# IIC.net
KiCad netlist of a schematic drawn in Altium Designer
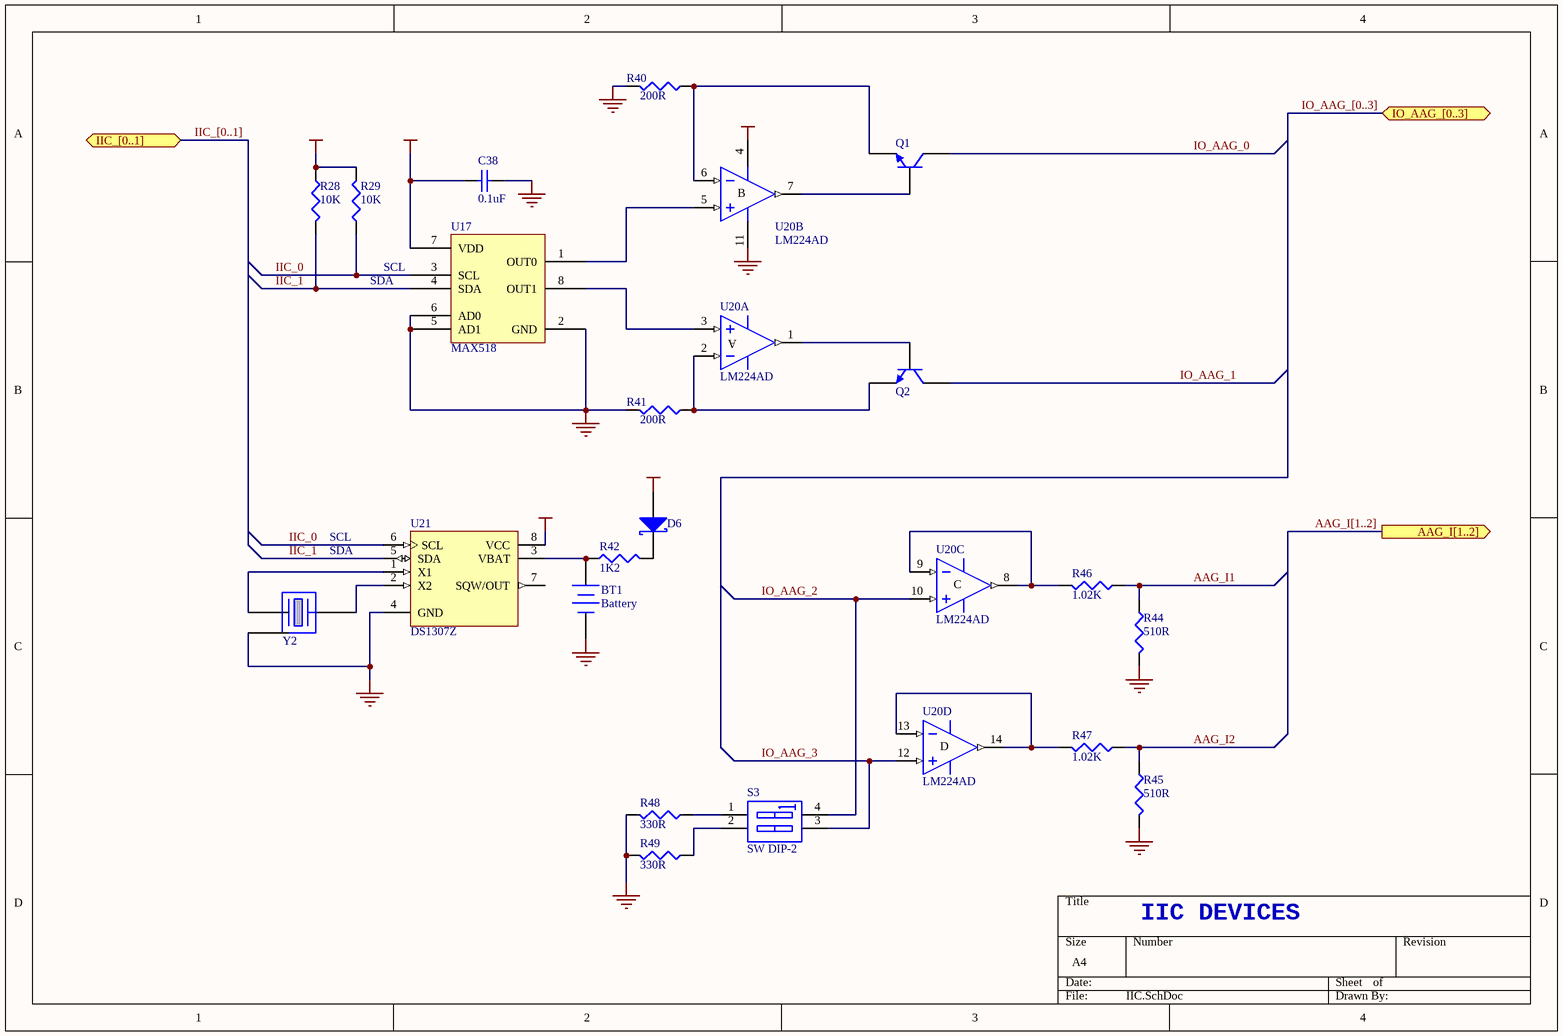
[diagram p0: IIC.SchDoc]

(export (version "E")
  (design (tool "Eeschema 10.0.6"))
  (components
    (comp (ref "BT1")
      (value "Battery")
      (footprint "LITHIUM_BAT")
      (description "Multicell Battery")
      (fields (field (name "PUBLISHER") "Altium Limited"))
      (libsource (lib "Miscellaneous Devices") (part "Battery"))
    )
    (comp (ref "C38")
      (value "0.1uF")
      (footprint "_0805")
      (description "Capacitor (Semiconductor SIM Model)")
      (fields (field (name "Comment") "Cap Semi") (field (name "PUBLISHER") "Altium Limited"))
      (libsource (lib "Miscellaneous Devices") (part "Cap Semi"))
    )
    (comp (ref "D6")
      (value "Diode BAS70")
      (footprint "SO-G3/C2.5")
      (description "Silicon AF Schottky Diode for High-Speed Switching")
      (fields (field (name "PUBLISHER") "Altium Limited"))
      (libsource (lib "Miscellaneous Devices") (part "Diode BAS70"))
    )
    (comp (ref "Q1")
      (value "QNPN")
      (footprint "SO-G3/C2.5")
      (description "NPN Bipolar Transistor")
      (fields (field (name "PUBLISHER") "Altium Limited"))
      (libsource (lib "") (part "QNPN_1"))
    )
    (comp (ref "Q2")
      (value "QNPN")
      (footprint "SO-G3/C2.5")
      (description "NPN Bipolar Transistor")
      (fields (field (name "PUBLISHER") "Altium Limited"))
      (libsource (lib "Miscellaneous Devices") (part "QNPN"))
    )
    (comp (ref "R28")
      (value "10K")
      (footprint "_0805")
      (description "Resistor")
      (fields (field (name "Comment") "Res3") (field (name "PUBLISHER") "Altium Limited"))
      (libsource (lib "") (part "Res3_1"))
    )
    (comp (ref "R29")
      (value "10K")
      (footprint "_0805")
      (description "Resistor")
      (fields (field (name "Comment") "Res3") (field (name "PUBLISHER") "Altium Limited"))
      (libsource (lib "") (part "Res3_1"))
    )
    (comp (ref "R40")
      (value "200R")
      (footprint "_1206")
      (description "Resistor")
      (fields (field (name "Comment") "Res3") (field (name "PUBLISHER") "Altium Limited"))
      (libsource (lib "") (part "Res3_1"))
    )
    (comp (ref "R41")
      (value "200R")
      (footprint "_1206")
      (description "Resistor")
      (fields (field (name "Comment") "Res3") (field (name "PUBLISHER") "Altium Limited"))
      (libsource (lib "") (part "Res3_1"))
    )
    (comp (ref "R42")
      (value "1K2")
      (footprint "_0805")
      (description "Resistor")
      (fields (field (name "Comment") "Res3") (field (name "PUBLISHER") "Altium Limited"))
      (libsource (lib "") (part "Res3_1"))
    )
    (comp (ref "R44")
      (value "510R")
      (footprint "_0805")
      (description "Resistor")
      (fields (field (name "Comment") "Res3") (field (name "PUBLISHER") "Altium Limited"))
      (libsource (lib "") (part "Res3_1"))
    )
    (comp (ref "R45")
      (value "510R")
      (footprint "_0805")
      (description "Resistor")
      (fields (field (name "Comment") "Res3") (field (name "PUBLISHER") "Altium Limited"))
      (libsource (lib "") (part "Res3_1"))
    )
    (comp (ref "R46")
      (value "1.02K")
      (footprint "_0805")
      (description "Resistor")
      (fields (field (name "Comment") "Res3") (field (name "PUBLISHER") "Altium Limited"))
      (libsource (lib "") (part "Res3_1"))
    )
    (comp (ref "R47")
      (value "1.02K")
      (footprint "_0805")
      (description "Resistor")
      (fields (field (name "Comment") "Res3") (field (name "PUBLISHER") "Altium Limited"))
      (libsource (lib "") (part "Res3_1"))
    )
    (comp (ref "R48")
      (value "330R")
      (footprint "_0805")
      (description "Resistor")
      (fields (field (name "Comment") "Res3") (field (name "PUBLISHER") "Altium Limited"))
      (libsource (lib "") (part "Res3_1"))
    )
    (comp (ref "R49")
      (value "330R")
      (footprint "_0805")
      (description "Resistor")
      (fields (field (name "Comment") "Res3") (field (name "PUBLISHER") "Altium Limited"))
      (libsource (lib "Miscellaneous Devices") (part "Res3"))
    )
    (comp (ref "S3")
      (value "SW DIP-2")
      (footprint "SWITCH_2SPST")
      (description "DIP Switch")
      (fields (field (name "PUBLISHER") "Altium Limited"))
      (libsource (lib "Miscellaneous Devices") (part "SW DIP-2"))
    )
    (comp (ref "U17")
      (value "MAX518")
      (footprint "SO-G8/D5")
      (description "2-Wire serial 8-bit DACs")
      (libsource (lib "Custom") (part "MAX518"))
    )
    (comp (ref "U20")
      (value "LM224AD")
      (footprint "SO14B")
      (description "Low-Power Quad Operational Amplifier")
      (fields (field (name "PUBLISHER") "Altium Limited"))
      (libsource (lib "ST Operational Amplifier") (part "LM324AD"))
    )
    (comp (ref "U21")
      (value "DS1307Z")
      (footprint "SOIC8N")
      (description "64 X 8 Serial Real-Time Clock")
      (fields (field (name "PUBLISHER") "Altium Limited"))
      (libsource (lib "Dallas Peripheral Real Time Clock") (part "DS1307Z"))
    )
    (comp (ref "Y2")
      (value "CRISTAL_SMD")
      (footprint "XTAL_32KHZ")
      (libsource (lib "Vending") (part "CRISTAL_SMD"))
    )
  )
  (nets
    (net (code "1") (name "/AAG_I1") (class "Default")
      (node (ref "R44") (pin "2") (pinfunction "2_2") (pintype "passive"))
      (node (ref "R46") (pin "2") (pinfunction "2_2") (pintype "passive"))
    )
    (net (code "2") (name "/AAG_I2") (class "Default")
      (node (ref "R45") (pin "2") (pinfunction "2_2") (pintype "passive"))
      (node (ref "R47") (pin "2") (pinfunction "2_2") (pintype "passive"))
    )
    (net (code "4") (name "/IIC_0") (class "Default")
      (node (ref "R29") (pin "1") (pinfunction "1_1") (pintype "passive"))
      (node (ref "U17") (pin "3") (pinfunction "SCL_3") (pintype "passive"))
      (node (ref "U21") (pin "6") (pinfunction "SCL_6") (pintype "input"))
    )
    (net (code "5") (name "/IIC_1") (class "Default")
      (node (ref "R28") (pin "2") (pinfunction "2_2") (pintype "passive"))
      (node (ref "U17") (pin "4") (pinfunction "SDA_4") (pintype "passive"))
      (node (ref "U21") (pin "5") (pinfunction "SDA_5") (pintype "bidirectional"))
    )
    (net (code "7") (name "/IO_AAG_0") (class "Default")
      (node (ref "Q1") (pin "3") (pinfunction "C_3") (pintype "passive"))
    )
    (net (code "8") (name "/IO_AAG_1") (class "Default")
      (node (ref "Q2") (pin "3") (pinfunction "C_3") (pintype "passive"))
    )
    (net (code "9") (name "/IO_AAG_2") (class "Default")
      (node (ref "S3") (pin "4") (pinfunction "B1_4") (pintype "passive"))
      (node (ref "U20") (pin "10") (pinfunction "IN+_10") (pintype "input"))
    )
    (net (code "10") (name "/IO_AAG_3") (class "Default")
      (node (ref "S3") (pin "3") (pinfunction "B2_3") (pintype "passive"))
      (node (ref "U20") (pin "12") (pinfunction "IN+_12") (pintype "input"))
    )
    (net (code "12") (name "GND") (class "Default")
      (node (ref "BT1") (pin "2") (pinfunction "-_2") (pintype "passive"))
      (node (ref "C38") (pin "2") (pinfunction "2_2") (pintype "passive"))
      (node (ref "R40") (pin "2") (pinfunction "2_2") (pintype "passive"))
      (node (ref "R41") (pin "2") (pinfunction "2_2") (pintype "passive"))
      (node (ref "R44") (pin "1") (pinfunction "1_1") (pintype "passive"))
      (node (ref "R45") (pin "1") (pinfunction "1_1") (pintype "passive"))
      (node (ref "R48") (pin "1") (pinfunction "1_1") (pintype "passive"))
      (node (ref "R49") (pin "1") (pinfunction "1_1") (pintype "passive"))
      (node (ref "U17") (pin "2") (pinfunction "GND_2") (pintype "passive"))
      (node (ref "U17") (pin "5") (pinfunction "AD1_5") (pintype "passive"))
      (node (ref "U17") (pin "6") (pinfunction "AD0_6") (pintype "passive"))
      (node (ref "U20") (pin "11") (pinfunction "V-_11") (pintype "power_in"))
      (node (ref "U21") (pin "4") (pinfunction "GND_4") (pintype "power_in"))
      (node (ref "Y2") (pin "0") (pintype "passive"))
    )
    (net (code "13") (name "Net-(BT1-+)") (class "Default")
      (node (ref "BT1") (pin "1") (pinfunction "+_1") (pintype "passive"))
      (node (ref "R42") (pin "1") (pinfunction "1_1") (pintype "passive"))
      (node (ref "U21") (pin "3") (pinfunction "VBAT_3") (pintype "power_in"))
    )
    (net (code "14") (name "Net-(D6-K)") (class "Default")
      (node (ref "D6") (pin "3") (pinfunction "K_3") (pintype "passive"))
      (node (ref "R42") (pin "2") (pinfunction "2_2") (pintype "passive"))
    )
    (net (code "15") (name "Net-(Q1-B)") (class "Default")
      (node (ref "Q1") (pin "1") (pinfunction "B_1") (pintype "passive"))
      (node (ref "U20") (pin "7") (pinfunction "OUT_7") (pintype "output"))
    )
    (net (code "16") (name "Net-(Q1-E)") (class "Default")
      (node (ref "Q1") (pin "2") (pinfunction "E_2") (pintype "passive"))
      (node (ref "R40") (pin "1") (pinfunction "1_1") (pintype "passive"))
      (node (ref "U20") (pin "6") (pinfunction "IN-_6") (pintype "input"))
    )
    (net (code "17") (name "Net-(Q2-B)") (class "Default")
      (node (ref "Q2") (pin "1") (pinfunction "B_1") (pintype "passive"))
      (node (ref "U20") (pin "1") (pinfunction "OUT_1") (pintype "output"))
    )
    (net (code "18") (name "Net-(Q2-E)") (class "Default")
      (node (ref "Q2") (pin "2") (pinfunction "E_2") (pintype "passive"))
      (node (ref "R41") (pin "1") (pinfunction "1_1") (pintype "passive"))
      (node (ref "U20") (pin "2") (pinfunction "IN-_2") (pintype "input"))
    )
    (net (code "19") (name "Net-(S3-A1)") (class "Default")
      (node (ref "R48") (pin "2") (pinfunction "2_2") (pintype "passive"))
      (node (ref "S3") (pin "1") (pinfunction "A1_1") (pintype "passive"))
    )
    (net (code "20") (name "Net-(S3-A2)") (class "Default")
      (node (ref "R49") (pin "2") (pinfunction "2_2") (pintype "passive"))
      (node (ref "S3") (pin "2") (pinfunction "A2_2") (pintype "passive"))
    )
    (net (code "21") (name "Net-(U17-OUT0)") (class "Default")
      (node (ref "U17") (pin "1") (pinfunction "OUT0_1") (pintype "passive"))
      (node (ref "U20") (pin "5") (pinfunction "IN+_5") (pintype "input"))
    )
    (net (code "22") (name "Net-(U17-OUT1)") (class "Default")
      (node (ref "U17") (pin "8") (pinfunction "OUT1_8") (pintype "passive"))
      (node (ref "U20") (pin "3") (pinfunction "IN+_3") (pintype "input"))
    )
    (net (code "23") (name "Net-(U20C-IN-)") (class "Default")
      (node (ref "R46") (pin "1") (pinfunction "1_1") (pintype "passive"))
      (node (ref "U20") (pin "8") (pinfunction "OUT_8") (pintype "output"))
      (node (ref "U20") (pin "9") (pinfunction "IN-_9") (pintype "input"))
    )
    (net (code "24") (name "Net-(U20D-IN-)") (class "Default")
      (node (ref "R47") (pin "1") (pinfunction "1_1") (pintype "passive"))
      (node (ref "U20") (pin "13") (pinfunction "IN-_13") (pintype "input"))
      (node (ref "U20") (pin "14") (pinfunction "OUT_14") (pintype "output"))
    )
    (net (code "25") (name "Net-(U21-X1)") (class "Default")
      (node (ref "U21") (pin "1") (pinfunction "X1_1") (pintype "input"))
      (node (ref "Y2") (pin "2") (pintype "passive"))
    )
    (net (code "26") (name "Net-(U21-X2)") (class "Default")
      (node (ref "U21") (pin "2") (pinfunction "X2_2") (pintype "input"))
      (node (ref "Y2") (pin "1") (pintype "passive"))
    )
    (net (code "27") (name "VCC_3V") (class "Default")
      (node (ref "D6") (pin "1") (pinfunction "A_1") (pintype "passive"))
      (node (ref "R28") (pin "1") (pinfunction "1_1") (pintype "passive"))
      (node (ref "R29") (pin "2") (pinfunction "2_2") (pintype "passive"))
    )
    (net (code "28") (name "VCC_5V") (class "Default")
      (node (ref "C38") (pin "1") (pinfunction "1_1") (pintype "passive"))
      (node (ref "U17") (pin "7") (pinfunction "VDD_7") (pintype "passive"))
      (node (ref "U21") (pin "8") (pinfunction "VCC_8") (pintype "power_in"))
    )
    (net (code "29") (name "VCC_IN") (class "Default")
      (node (ref "U20") (pin "4") (pinfunction "V+_4") (pintype "power_in"))
    )
    (net (code "30") (name "unconnected-(U21-SQW{slash}OUT-Pad7)") (class "Default")
      (node (ref "U21") (pin "7") (pinfunction "SQW/OUT_7") (pintype "output"))
    )
  )
)
